# Aux_Outputs.net
KiCad netlist of a schematic drawn in Altium Designer
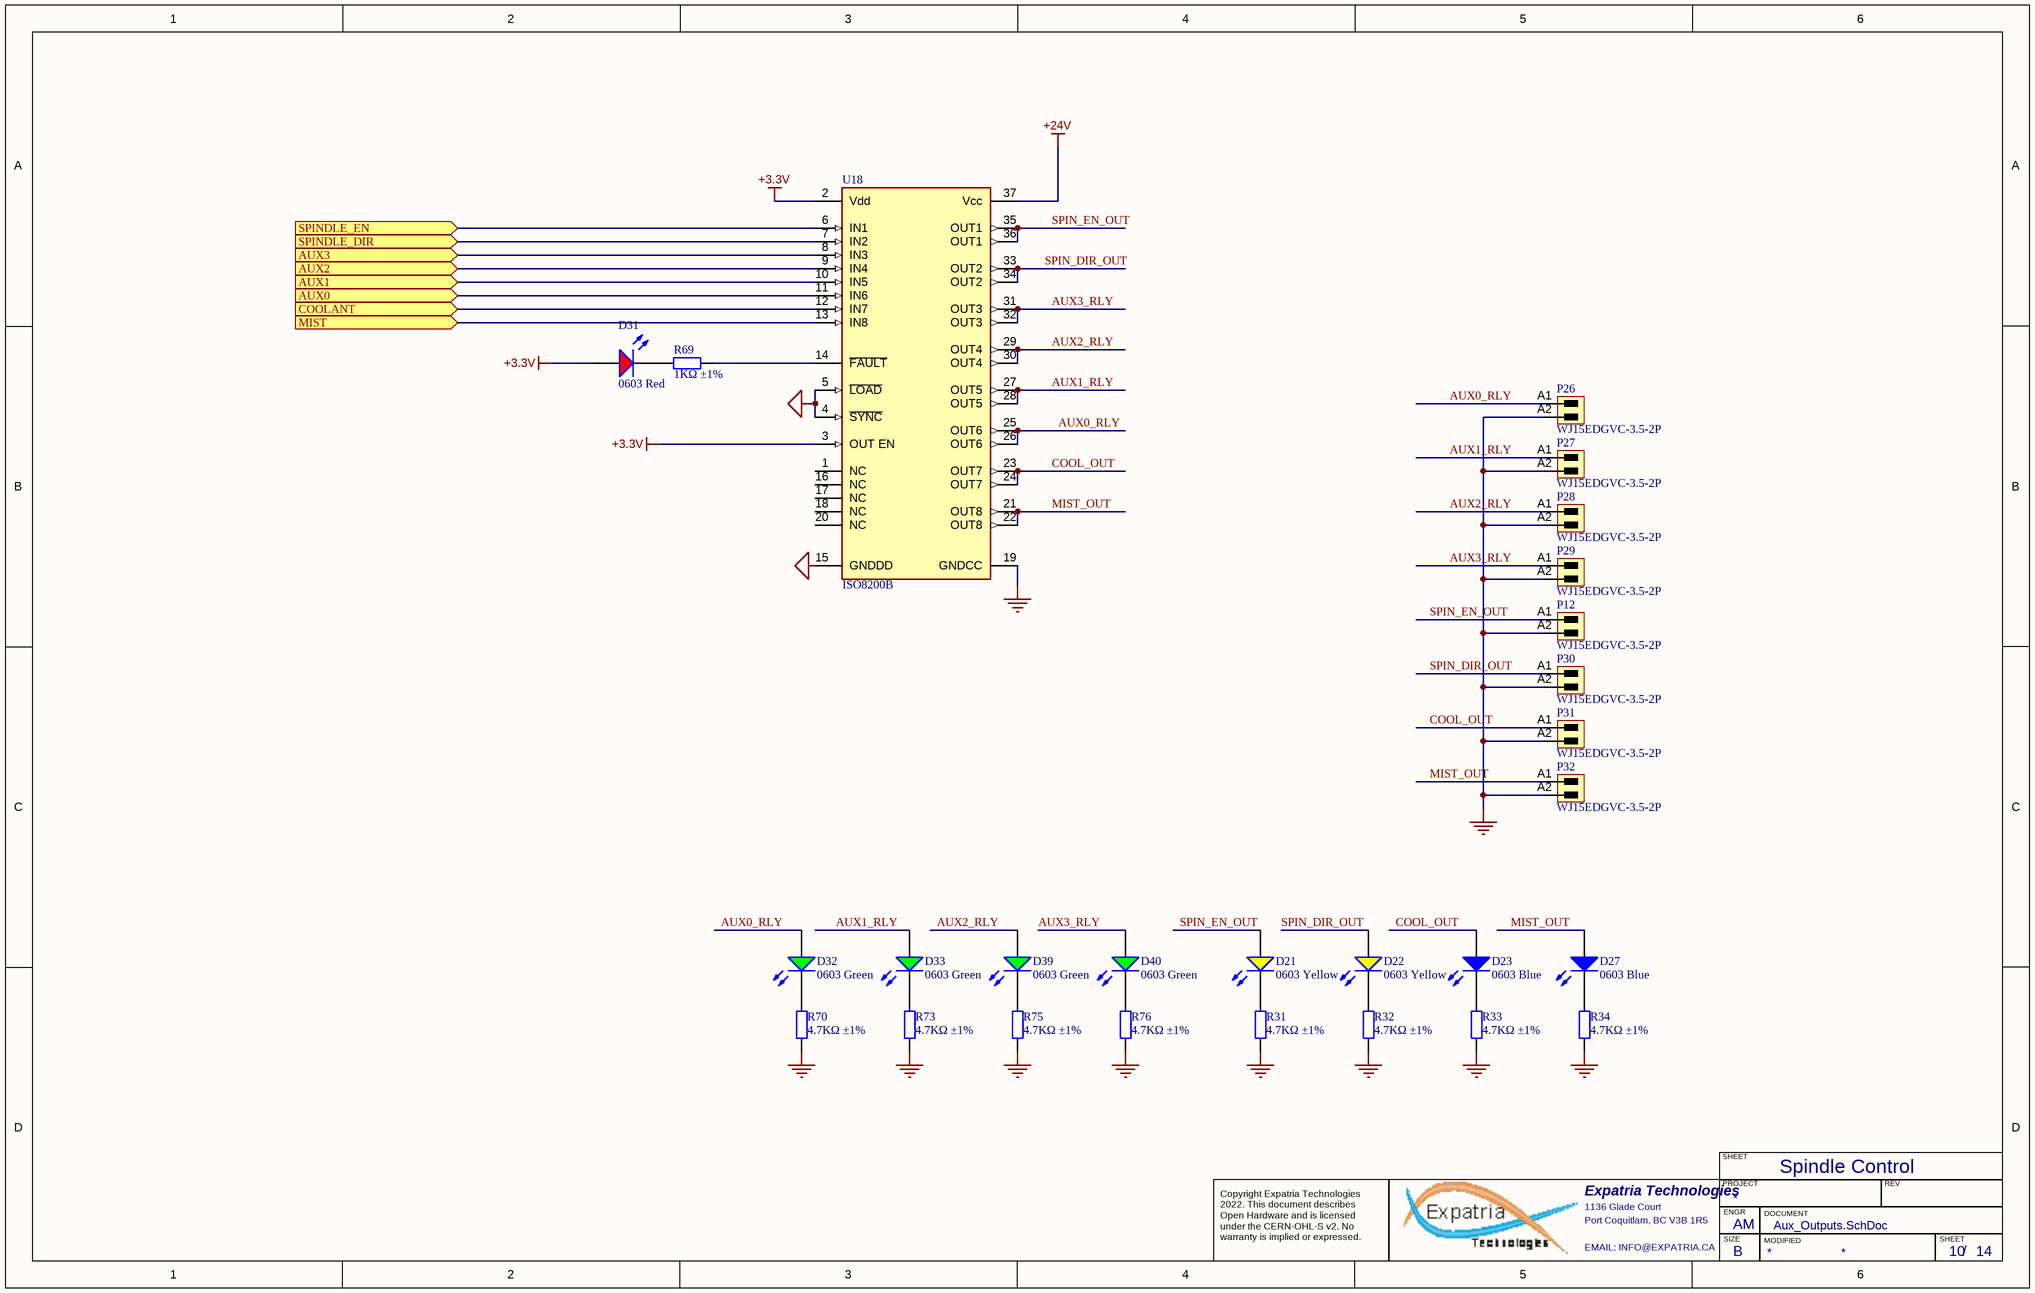
[diagram p0: Aux_Outputs.SchDoc]

(export (version "E")
  (design (tool "Eeschema 10.0.6"))
  (components
    (comp (ref "D21")
      (value "0603 Yellow")
      (footprint "0603_LED_S1")
      (description "LED")
      (libsource (lib "LED") (part "0603 LED Yellow"))
    )
    (comp (ref "D22")
      (value "0603 Yellow")
      (footprint "0603_LED_S1")
      (description "LED")
      (libsource (lib "LED") (part "0603 LED Yellow"))
    )
    (comp (ref "D23")
      (value "0603 Blue")
      (footprint "0603_LED_S1")
      (description "LED")
      (libsource (lib "LED") (part "0603 LED Blue"))
    )
    (comp (ref "D27")
      (value "0603 Blue")
      (footprint "0603_LED_S1")
      (description "LED")
      (libsource (lib "LED") (part "0603 LED Blue"))
    )
    (comp (ref "D31")
      (value "0603 Red")
      (footprint "0603_LED_S1")
      (description "LED")
      (libsource (lib "LED") (part "0603 LED Red"))
    )
    (comp (ref "D32")
      (value "0603 Green")
      (footprint "0603_LED_S1")
      (description "LED")
      (libsource (lib "LED") (part "0603 LED Green"))
    )
    (comp (ref "D33")
      (value "0603 Green")
      (footprint "0603_LED_S1")
      (description "LED")
      (libsource (lib "LED") (part "0603 LED Green"))
    )
    (comp (ref "D39")
      (value "0603 Green")
      (footprint "0603_LED_S1")
      (description "LED")
      (libsource (lib "LED") (part "0603 LED Green"))
    )
    (comp (ref "D40")
      (value "0603 Green")
      (footprint "0603_LED_S1")
      (description "LED")
      (libsource (lib "LED") (part "0603 LED Green"))
    )
    (comp (ref "P12")
      (value "WJ15EDGVC-3.5-2P")
      (footprint "691321100002")
      (fields (field (name "MANUFACTURER") "Weidmueller"))
      (libsource (lib "Universal_CNC_Breakout") (part "3.5mm Terminal Header 2p"))
    )
    (comp (ref "P26")
      (value "WJ15EDGVC-3.5-2P")
      (footprint "691321100002")
      (fields (field (name "MANUFACTURER") "Weidmueller"))
      (libsource (lib "Universal_CNC_Breakout") (part "3.5mm Terminal Header 2p"))
    )
    (comp (ref "P27")
      (value "WJ15EDGVC-3.5-2P")
      (footprint "691321100002")
      (fields (field (name "MANUFACTURER") "Weidmueller"))
      (libsource (lib "Universal_CNC_Breakout") (part "3.5mm Terminal Header 2p"))
    )
    (comp (ref "P28")
      (value "WJ15EDGVC-3.5-2P")
      (footprint "691321100002")
      (fields (field (name "MANUFACTURER") "Weidmueller"))
      (libsource (lib "Universal_CNC_Breakout") (part "3.5mm Terminal Header 2p"))
    )
    (comp (ref "P29")
      (value "WJ15EDGVC-3.5-2P")
      (footprint "691321100002")
      (fields (field (name "MANUFACTURER") "Weidmueller"))
      (libsource (lib "Universal_CNC_Breakout") (part "3.5mm Terminal Header 2p"))
    )
    (comp (ref "P30")
      (value "WJ15EDGVC-3.5-2P")
      (footprint "691321100002")
      (fields (field (name "MANUFACTURER") "Weidmueller"))
      (libsource (lib "Universal_CNC_Breakout") (part "3.5mm Terminal Header 2p"))
    )
    (comp (ref "P31")
      (value "WJ15EDGVC-3.5-2P")
      (footprint "691321100002")
      (fields (field (name "MANUFACTURER") "Weidmueller"))
      (libsource (lib "Universal_CNC_Breakout") (part "3.5mm Terminal Header 2p"))
    )
    (comp (ref "P32")
      (value "WJ15EDGVC-3.5-2P")
      (footprint "691321100002")
      (fields (field (name "MANUFACTURER") "Weidmueller"))
      (libsource (lib "Universal_CNC_Breakout") (part "3.5mm Terminal Header 2p"))
    )
    (comp (ref "R31")
      (value "4.7KΩ ±1%")
      (footprint "0402_R")
      (description "Chip resistor")
      (fields (field (name "MANUFACTURER") "Uniroyal Elec") (field (name "PARTNUMBER") "0402WGF4701TCE"))
      (libsource (lib "RES") (part "0402 4.7K (4701) 1%"))
    )
    (comp (ref "R32")
      (value "4.7KΩ ±1%")
      (footprint "0402_R")
      (description "Chip resistor")
      (fields (field (name "MANUFACTURER") "Uniroyal Elec") (field (name "PARTNUMBER") "0402WGF4701TCE"))
      (libsource (lib "RES") (part "0402 4.7K (4701) 1%"))
    )
    (comp (ref "R33")
      (value "4.7KΩ ±1%")
      (footprint "0402_R")
      (description "Chip resistor")
      (fields (field (name "MANUFACTURER") "Uniroyal Elec") (field (name "PARTNUMBER") "0402WGF4701TCE"))
      (libsource (lib "RES") (part "0402 4.7K (4701) 1%"))
    )
    (comp (ref "R34")
      (value "4.7KΩ ±1%")
      (footprint "0402_R")
      (description "Chip resistor")
      (fields (field (name "MANUFACTURER") "Uniroyal Elec") (field (name "PARTNUMBER") "0402WGF4701TCE"))
      (libsource (lib "RES") (part "0402 4.7K (4701) 1%"))
    )
    (comp (ref "R69")
      (value "1KΩ ±1%")
      (footprint "0402_R")
      (description "Chip resistor")
      (fields (field (name "MANUFACTURER") "Uniroyal Elec") (field (name "PARTNUMBER") "0402WGF1001TCE"))
      (libsource (lib "RES") (part "0402 1K (1001) 1%"))
    )
    (comp (ref "R70")
      (value "4.7KΩ ±1%")
      (footprint "0402_R")
      (description "Chip resistor")
      (fields (field (name "MANUFACTURER") "Uniroyal Elec") (field (name "PARTNUMBER") "0402WGF4701TCE"))
      (libsource (lib "RES") (part "0402 4.7K (4701) 1%"))
    )
    (comp (ref "R73")
      (value "4.7KΩ ±1%")
      (footprint "0402_R")
      (description "Chip resistor")
      (fields (field (name "MANUFACTURER") "Uniroyal Elec") (field (name "PARTNUMBER") "0402WGF4701TCE"))
      (libsource (lib "RES") (part "0402 4.7K (4701) 1%"))
    )
    (comp (ref "R75")
      (value "4.7KΩ ±1%")
      (footprint "0402_R")
      (description "Chip resistor")
      (fields (field (name "MANUFACTURER") "Uniroyal Elec") (field (name "PARTNUMBER") "0402WGF4701TCE"))
      (libsource (lib "RES") (part "0402 4.7K (4701) 1%"))
    )
    (comp (ref "R76")
      (value "4.7KΩ ±1%")
      (footprint "0402_R")
      (description "Chip resistor")
      (fields (field (name "MANUFACTURER") "Uniroyal Elec") (field (name "PARTNUMBER") "0402WGF4701TCE"))
      (libsource (lib "RES") (part "0402 4.7K (4701) 1%"))
    )
    (comp (ref "U18")
      (value "ISO8200B")
      (footprint "FP-PowerSO-36-MFG")
      (description "IC PWR DRIVER 1:1 PWRSO36")
      (fields
        (field (name "MANUFACTURER") "STMicroelectronics")
        (field (name "OCTOPART") "https://octopart.com/iso8200b-stmicroelectronics-30038077")
      )
      (libsource (lib "Altium Content Vault") (part "bb7b40fea314a9fcc47e7ab39391371"))
    )
  )
  (nets
    (net (code "1") (name "+3.3V") (class "Default")
      (node (ref "D31") (pin "A") (pinfunction "A_A") (pintype "passive"))
      (node (ref "U18") (pin "2") (pinfunction "Vdd_2") (pintype "power_in"))
      (node (ref "U18") (pin "3") (pinfunction "OUT_EN_3") (pintype "input"))
    )
    (net (code "2") (name "+24V") (class "Default")
      (node (ref "U18") (pin "37") (pinfunction "Vcc_37") (pintype "power_in"))
    )
    (net (code "3") (name "/AUX0") (class "Default")
      (node (ref "U18") (pin "11") (pinfunction "IN6_11") (pintype "input"))
    )
    (net (code "4") (name "/AUX0_RLY") (class "Default")
      (node (ref "D32") (pin "A") (pinfunction "A_A") (pintype "passive"))
      (node (ref "P26") (pin "A1") (pinfunction "A1_A1") (pintype "passive"))
      (node (ref "U18") (pin "25") (pinfunction "OUT6_25") (pintype "output"))
      (node (ref "U18") (pin "26") (pinfunction "OUT6_26") (pintype "output"))
    )
    (net (code "5") (name "/AUX1") (class "Default")
      (node (ref "U18") (pin "10") (pinfunction "IN5_10") (pintype "input"))
    )
    (net (code "6") (name "/AUX1_RLY") (class "Default")
      (node (ref "D33") (pin "A") (pinfunction "A_A") (pintype "passive"))
      (node (ref "P27") (pin "A1") (pinfunction "A1_A1") (pintype "passive"))
      (node (ref "U18") (pin "27") (pinfunction "OUT5_27") (pintype "output"))
      (node (ref "U18") (pin "28") (pinfunction "OUT5_28") (pintype "output"))
    )
    (net (code "7") (name "/AUX2") (class "Default")
      (node (ref "U18") (pin "9") (pinfunction "IN4_9") (pintype "input"))
    )
    (net (code "8") (name "/AUX2_RLY") (class "Default")
      (node (ref "D39") (pin "A") (pinfunction "A_A") (pintype "passive"))
      (node (ref "P28") (pin "A1") (pinfunction "A1_A1") (pintype "passive"))
      (node (ref "U18") (pin "29") (pinfunction "OUT4_29") (pintype "output"))
      (node (ref "U18") (pin "30") (pinfunction "OUT4_30") (pintype "output"))
    )
    (net (code "9") (name "/AUX3") (class "Default")
      (node (ref "U18") (pin "8") (pinfunction "IN3_8") (pintype "input"))
    )
    (net (code "10") (name "/AUX3_RLY") (class "Default")
      (node (ref "D40") (pin "A") (pinfunction "A_A") (pintype "passive"))
      (node (ref "P29") (pin "A1") (pinfunction "A1_A1") (pintype "passive"))
      (node (ref "U18") (pin "31") (pinfunction "OUT3_31") (pintype "output"))
      (node (ref "U18") (pin "32") (pinfunction "OUT3_32") (pintype "output"))
    )
    (net (code "11") (name "/COOLANT") (class "Default")
      (node (ref "U18") (pin "12") (pinfunction "IN7_12") (pintype "input"))
    )
    (net (code "12") (name "/COOL_OUT") (class "Default")
      (node (ref "D23") (pin "A") (pinfunction "A_A") (pintype "passive"))
      (node (ref "P31") (pin "A1") (pinfunction "A1_A1") (pintype "passive"))
      (node (ref "U18") (pin "23") (pinfunction "OUT7_23") (pintype "output"))
      (node (ref "U18") (pin "24") (pinfunction "OUT7_24") (pintype "output"))
    )
    (net (code "13") (name "/MIST") (class "Default")
      (node (ref "U18") (pin "13") (pinfunction "IN8_13") (pintype "input"))
    )
    (net (code "14") (name "/MIST_OUT") (class "Default")
      (node (ref "D27") (pin "A") (pinfunction "A_A") (pintype "passive"))
      (node (ref "P32") (pin "A1") (pinfunction "A1_A1") (pintype "passive"))
      (node (ref "U18") (pin "21") (pinfunction "OUT8_21") (pintype "output"))
      (node (ref "U18") (pin "22") (pinfunction "OUT8_22") (pintype "output"))
    )
    (net (code "15") (name "/SPINDLE_DIR") (class "Default")
      (node (ref "U18") (pin "7") (pinfunction "IN2_7") (pintype "input"))
    )
    (net (code "16") (name "/SPINDLE_EN") (class "Default")
      (node (ref "U18") (pin "6") (pinfunction "IN1_6") (pintype "input"))
    )
    (net (code "17") (name "/SPIN_DIR_OUT") (class "Default")
      (node (ref "D22") (pin "A") (pinfunction "A_A") (pintype "passive"))
      (node (ref "P30") (pin "A1") (pinfunction "A1_A1") (pintype "passive"))
      (node (ref "U18") (pin "33") (pinfunction "OUT2_33") (pintype "output"))
      (node (ref "U18") (pin "34") (pinfunction "OUT2_34") (pintype "output"))
    )
    (net (code "18") (name "/SPIN_EN_OUT") (class "Default")
      (node (ref "D21") (pin "A") (pinfunction "A_A") (pintype "passive"))
      (node (ref "P12") (pin "A1") (pinfunction "A1_A1") (pintype "passive"))
      (node (ref "U18") (pin "35") (pinfunction "OUT1_35") (pintype "output"))
      (node (ref "U18") (pin "36") (pinfunction "OUT1_36") (pintype "output"))
    )
    (net (code "19") (name "GND") (class "Default")
      (node (ref "P12") (pin "A2") (pinfunction "A2_A2") (pintype "passive"))
      (node (ref "P26") (pin "A2") (pinfunction "A2_A2") (pintype "passive"))
      (node (ref "P27") (pin "A2") (pinfunction "A2_A2") (pintype "passive"))
      (node (ref "P28") (pin "A2") (pinfunction "A2_A2") (pintype "passive"))
      (node (ref "P29") (pin "A2") (pinfunction "A2_A2") (pintype "passive"))
      (node (ref "P30") (pin "A2") (pinfunction "A2_A2") (pintype "passive"))
      (node (ref "P31") (pin "A2") (pinfunction "A2_A2") (pintype "passive"))
      (node (ref "P32") (pin "A2") (pinfunction "A2_A2") (pintype "passive"))
      (node (ref "R31") (pin "1") (pinfunction "1_1") (pintype "passive"))
      (node (ref "R32") (pin "1") (pinfunction "1_1") (pintype "passive"))
      (node (ref "R33") (pin "1") (pinfunction "1_1") (pintype "passive"))
      (node (ref "R34") (pin "1") (pinfunction "1_1") (pintype "passive"))
      (node (ref "R70") (pin "1") (pinfunction "1_1") (pintype "passive"))
      (node (ref "R73") (pin "1") (pinfunction "1_1") (pintype "passive"))
      (node (ref "R75") (pin "1") (pinfunction "1_1") (pintype "passive"))
      (node (ref "R76") (pin "1") (pinfunction "1_1") (pintype "passive"))
      (node (ref "U18") (pin "19") (pinfunction "GNDCC_19") (pintype "power_in"))
    )
    (net (code "20") (name "MCU_GND") (class "Default")
      (node (ref "U18") (pin "15") (pinfunction "GNDDD_15") (pintype "power_in"))
      (node (ref "U18") (pin "4") (pinfunction "~{SYNC}_4") (pintype "input"))
      (node (ref "U18") (pin "5") (pinfunction "~{LOAD}_5") (pintype "input"))
    )
    (net (code "21") (name "Net-(D21-PadK)") (class "Default")
      (node (ref "D21") (pin "K") (pinfunction "K_K") (pintype "passive"))
      (node (ref "R31") (pin "2") (pinfunction "2_2") (pintype "passive"))
    )
    (net (code "22") (name "Net-(D22-PadK)") (class "Default")
      (node (ref "D22") (pin "K") (pinfunction "K_K") (pintype "passive"))
      (node (ref "R32") (pin "2") (pinfunction "2_2") (pintype "passive"))
    )
    (net (code "23") (name "Net-(D23-PadK)") (class "Default")
      (node (ref "D23") (pin "K") (pinfunction "K_K") (pintype "passive"))
      (node (ref "R33") (pin "2") (pinfunction "2_2") (pintype "passive"))
    )
    (net (code "24") (name "Net-(D27-PadK)") (class "Default")
      (node (ref "D27") (pin "K") (pinfunction "K_K") (pintype "passive"))
      (node (ref "R34") (pin "2") (pinfunction "2_2") (pintype "passive"))
    )
    (net (code "25") (name "Net-(D31-PadK)") (class "Default")
      (node (ref "D31") (pin "K") (pinfunction "K_K") (pintype "passive"))
      (node (ref "R69") (pin "1") (pinfunction "1_1") (pintype "passive"))
    )
    (net (code "26") (name "Net-(D32-PadK)") (class "Default")
      (node (ref "D32") (pin "K") (pinfunction "K_K") (pintype "passive"))
      (node (ref "R70") (pin "2") (pinfunction "2_2") (pintype "passive"))
    )
    (net (code "27") (name "Net-(D33-PadK)") (class "Default")
      (node (ref "D33") (pin "K") (pinfunction "K_K") (pintype "passive"))
      (node (ref "R73") (pin "2") (pinfunction "2_2") (pintype "passive"))
    )
    (net (code "28") (name "Net-(D39-PadK)") (class "Default")
      (node (ref "D39") (pin "K") (pinfunction "K_K") (pintype "passive"))
      (node (ref "R75") (pin "2") (pinfunction "2_2") (pintype "passive"))
    )
    (net (code "29") (name "Net-(D40-PadK)") (class "Default")
      (node (ref "D40") (pin "K") (pinfunction "K_K") (pintype "passive"))
      (node (ref "R76") (pin "2") (pinfunction "2_2") (pintype "passive"))
    )
    (net (code "30") (name "Net-(U18-~{FAULT})") (class "Default")
      (node (ref "R69") (pin "2") (pinfunction "2_2") (pintype "passive"))
      (node (ref "U18") (pin "14") (pinfunction "~{FAULT}_14") (pintype "open_collector"))
    )
    (net (code "31") (name "unconnected-(U18-NC-Pad1)") (class "Default")
      (node (ref "U18") (pin "1") (pinfunction "NC_1") (pintype "passive"))
    )
    (net (code "32") (name "unconnected-(U18-NC-Pad16)") (class "Default")
      (node (ref "U18") (pin "16") (pinfunction "NC_16") (pintype "passive"))
    )
    (net (code "33") (name "unconnected-(U18-NC-Pad17)") (class "Default")
      (node (ref "U18") (pin "17") (pinfunction "NC_17") (pintype "passive"))
    )
    (net (code "34") (name "unconnected-(U18-NC-Pad18)") (class "Default")
      (node (ref "U18") (pin "18") (pinfunction "NC_18") (pintype "passive"))
    )
    (net (code "35") (name "unconnected-(U18-NC-Pad20)") (class "Default")
      (node (ref "U18") (pin "20") (pinfunction "NC_20") (pintype "passive"))
    )
  )
)
